# cpuboard.net
KiCad netlist of a schematic drawn in Altium Designer
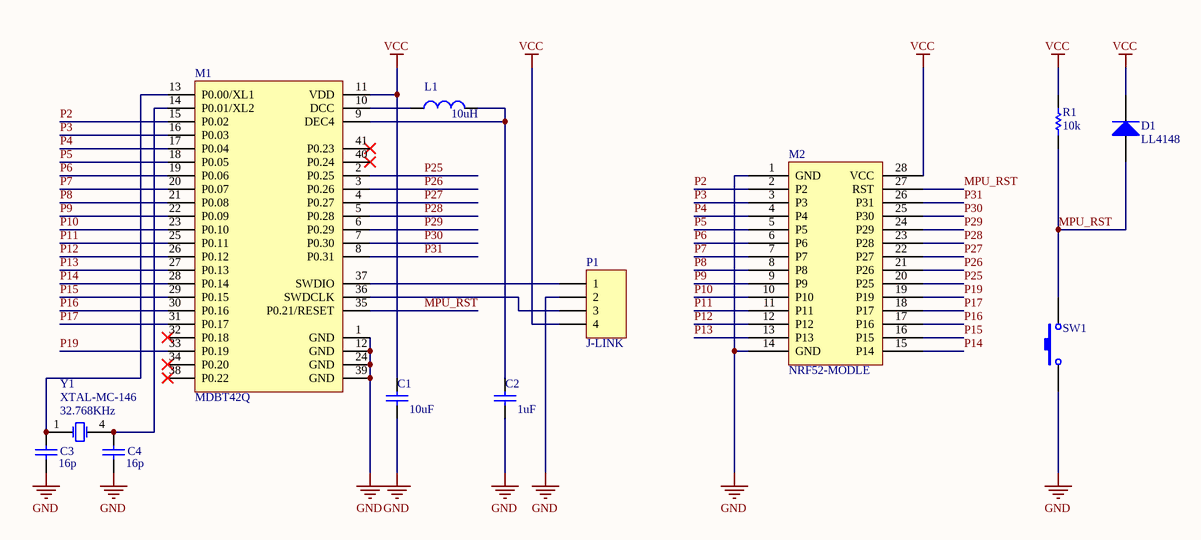
[diagram p0: cpuboard.SchDoc]

(export (version "E")
  (design (tool "Eeschema 10.0.6"))
  (components
    (comp (ref "C1")
      (value "10uF")
      (footprint "1608[0603]")
      (fields (field (name "Comment") "Cap1"))
      (libsource (lib "Other") (part "Cap1"))
    )
    (comp (ref "C2")
      (value "1uF")
      (footprint "1608[0603]")
      (fields (field (name "Comment") "Cap1"))
      (libsource (lib "Other") (part "Cap1"))
    )
    (comp (ref "C3")
      (value "16p")
      (footprint "1608[0603]")
      (fields (field (name "Comment") "Cap1"))
      (libsource (lib "Other") (part "Cap1"))
    )
    (comp (ref "C4")
      (value "16p")
      (footprint "1608[0603]")
      (fields (field (name "Comment") "Cap1"))
      (libsource (lib "Other") (part "Cap1"))
    )
    (comp (ref "D1") (value "LL4148") (footprint "SOD80") (libsource (lib "Diode") (part "LL4148")))
    (comp (ref "L1")
      (value "10uH")
      (footprint "2012[0805]")
      (fields (field (name "Comment") "Inductor"))
      (libsource (lib "Other") (part "Inductor"))
    )
    (comp (ref "M1") (value "MDBT42Q") (footprint "MDBT42Q") (libsource (lib "Module") (part "MDBT42Q")))
    (comp (ref "M2")
      (value "NRF52-MODLE")
      (footprint "NRF52-MODLE")
      (libsource (lib "newlib") (part "NRF52-MODLE"))
    )
    (comp (ref "P1")
      (value "J-LINK")
      (footprint "HDR1X4")
      (description "Header, 4-Pin")
      (fields (field (name "PUBLISHER") "Altium Limited"))
      (libsource (lib "Connector") (part "Header 4"))
    )
    (comp (ref "R1")
      (value "10k")
      (footprint "1608[0603]")
      (fields (field (name "Comment") "Res"))
      (libsource (lib "Other") (part "Res"))
    )
    (comp (ref "SW1")
      (value "TL3342F160QG")
      (footprint "TL3342F160QG")
      (libsource (lib "Switch") (part "TL3342F160QG"))
    )
    (comp (ref "Y1")
      (value "XTAL-MC-146")
      (footprint "MC-146")
      (fields (field (name "ALTIUM_VALUE") "32.768KHz"))
      (libsource (lib "Signal") (part "XTAL-MC-146"))
    )
  )
  (nets
    (net (code "1") (name "/MPU_RST") (class "Default")
      (node (ref "D1") (pin "1") (pinfunction "A_1") (pintype "passive"))
      (node (ref "M1") (pin "35") (pinfunction "P0.21/RESET_35") (pintype "passive"))
      (node (ref "M2") (pin "27") (pinfunction "RST_27") (pintype "passive"))
      (node (ref "R1") (pin "2") (pinfunction "2_2") (pintype "passive"))
      (node (ref "SW1") (pin "3") (pinfunction "3_3") (pintype "passive"))
    )
    (net (code "2") (name "/P2") (class "Default")
      (node (ref "M1") (pin "15") (pinfunction "P0.02_15") (pintype "passive"))
      (node (ref "M2") (pin "2") (pinfunction "P2_2") (pintype "passive"))
    )
    (net (code "3") (name "/P3") (class "Default")
      (node (ref "M1") (pin "16") (pinfunction "P0.03_16") (pintype "passive"))
      (node (ref "M2") (pin "3") (pinfunction "P3_3") (pintype "passive"))
    )
    (net (code "4") (name "/P4") (class "Default")
      (node (ref "M1") (pin "17") (pinfunction "P0.04_17") (pintype "passive"))
      (node (ref "M2") (pin "4") (pinfunction "P4_4") (pintype "passive"))
    )
    (net (code "5") (name "/P5") (class "Default")
      (node (ref "M1") (pin "18") (pinfunction "P0.05_18") (pintype "passive"))
      (node (ref "M2") (pin "5") (pinfunction "P5_5") (pintype "passive"))
    )
    (net (code "6") (name "/P6") (class "Default")
      (node (ref "M1") (pin "19") (pinfunction "P0.06_19") (pintype "passive"))
      (node (ref "M2") (pin "6") (pinfunction "P6_6") (pintype "passive"))
    )
    (net (code "7") (name "/P7") (class "Default")
      (node (ref "M1") (pin "20") (pinfunction "P0.07_20") (pintype "passive"))
      (node (ref "M2") (pin "7") (pinfunction "P7_7") (pintype "passive"))
    )
    (net (code "8") (name "/P8") (class "Default")
      (node (ref "M1") (pin "21") (pinfunction "P0.08_21") (pintype "passive"))
      (node (ref "M2") (pin "8") (pinfunction "P8_8") (pintype "passive"))
    )
    (net (code "9") (name "/P9") (class "Default")
      (node (ref "M1") (pin "22") (pinfunction "P0.09_22") (pintype "passive"))
      (node (ref "M2") (pin "9") (pinfunction "P9_9") (pintype "passive"))
    )
    (net (code "10") (name "/P10") (class "Default")
      (node (ref "M1") (pin "23") (pinfunction "P0.10_23") (pintype "passive"))
      (node (ref "M2") (pin "10") (pinfunction "P10_10") (pintype "passive"))
    )
    (net (code "11") (name "/P11") (class "Default")
      (node (ref "M1") (pin "25") (pinfunction "P0.11_25") (pintype "passive"))
      (node (ref "M2") (pin "11") (pinfunction "P11_11") (pintype "passive"))
    )
    (net (code "12") (name "/P12") (class "Default")
      (node (ref "M1") (pin "26") (pinfunction "P0.12_26") (pintype "passive"))
      (node (ref "M2") (pin "12") (pinfunction "P12_12") (pintype "passive"))
    )
    (net (code "13") (name "/P13") (class "Default")
      (node (ref "M1") (pin "27") (pinfunction "P0.13_27") (pintype "passive"))
      (node (ref "M2") (pin "13") (pinfunction "P13_13") (pintype "passive"))
    )
    (net (code "14") (name "/P14") (class "Default")
      (node (ref "M1") (pin "28") (pinfunction "P0.14_28") (pintype "passive"))
      (node (ref "M2") (pin "15") (pinfunction "P14_15") (pintype "passive"))
    )
    (net (code "15") (name "/P15") (class "Default")
      (node (ref "M1") (pin "29") (pinfunction "P0.15_29") (pintype "passive"))
      (node (ref "M2") (pin "16") (pinfunction "P15_16") (pintype "passive"))
    )
    (net (code "16") (name "/P16") (class "Default")
      (node (ref "M1") (pin "30") (pinfunction "P0.16_30") (pintype "passive"))
      (node (ref "M2") (pin "17") (pinfunction "P16_17") (pintype "passive"))
    )
    (net (code "17") (name "/P17") (class "Default")
      (node (ref "M1") (pin "31") (pinfunction "P0.17_31") (pintype "passive"))
      (node (ref "M2") (pin "18") (pinfunction "P17_18") (pintype "passive"))
    )
    (net (code "18") (name "/P19") (class "Default")
      (node (ref "M1") (pin "33") (pinfunction "P0.19_33") (pintype "passive"))
      (node (ref "M2") (pin "19") (pinfunction "P19_19") (pintype "passive"))
    )
    (net (code "19") (name "/P25") (class "Default")
      (node (ref "M1") (pin "2") (pinfunction "P0.25_2") (pintype "passive"))
      (node (ref "M2") (pin "20") (pinfunction "P25_20") (pintype "passive"))
    )
    (net (code "20") (name "/P26") (class "Default")
      (node (ref "M1") (pin "3") (pinfunction "P0.26_3") (pintype "passive"))
      (node (ref "M2") (pin "21") (pinfunction "P26_21") (pintype "passive"))
    )
    (net (code "21") (name "/P27") (class "Default")
      (node (ref "M1") (pin "4") (pinfunction "P0.27_4") (pintype "passive"))
      (node (ref "M2") (pin "22") (pinfunction "P27_22") (pintype "passive"))
    )
    (net (code "22") (name "/P28") (class "Default")
      (node (ref "M1") (pin "5") (pinfunction "P0.28_5") (pintype "passive"))
      (node (ref "M2") (pin "23") (pinfunction "P28_23") (pintype "passive"))
    )
    (net (code "23") (name "/P29") (class "Default")
      (node (ref "M1") (pin "6") (pinfunction "P0.29_6") (pintype "passive"))
      (node (ref "M2") (pin "24") (pinfunction "P29_24") (pintype "passive"))
    )
    (net (code "24") (name "/P30") (class "Default")
      (node (ref "M1") (pin "7") (pinfunction "P0.30_7") (pintype "passive"))
      (node (ref "M2") (pin "25") (pinfunction "P30_25") (pintype "passive"))
    )
    (net (code "25") (name "/P31") (class "Default")
      (node (ref "M1") (pin "8") (pinfunction "P0.31_8") (pintype "passive"))
      (node (ref "M2") (pin "26") (pinfunction "P31_26") (pintype "passive"))
    )
    (net (code "26") (name "GND") (class "Default")
      (node (ref "C1") (pin "1") (pinfunction "1_1") (pintype "passive"))
      (node (ref "C2") (pin "1") (pinfunction "1_1") (pintype "passive"))
      (node (ref "C3") (pin "1") (pinfunction "1_1") (pintype "passive"))
      (node (ref "C4") (pin "1") (pinfunction "1_1") (pintype "passive"))
      (node (ref "M1") (pin "1") (pinfunction "GND_1") (pintype "passive"))
      (node (ref "M1") (pin "12") (pinfunction "GND_12") (pintype "passive"))
      (node (ref "M1") (pin "24") (pinfunction "GND_24") (pintype "passive"))
      (node (ref "M1") (pin "39") (pinfunction "GND_39") (pintype "passive"))
      (node (ref "M2") (pin "1") (pinfunction "GND_1") (pintype "passive"))
      (node (ref "M2") (pin "14") (pinfunction "GND_14") (pintype "passive"))
      (node (ref "P1") (pin "2") (pinfunction "2_2") (pintype "passive"))
      (node (ref "SW1") (pin "1") (pinfunction "1_1") (pintype "passive"))
    )
    (net (code "27") (name "Net-(M1-DCC)") (class "Default")
      (node (ref "L1") (pin "1") (pinfunction "1_1") (pintype "passive"))
      (node (ref "M1") (pin "10") (pinfunction "DCC_10") (pintype "passive"))
    )
    (net (code "28") (name "Net-(M1-DEC4)") (class "Default")
      (node (ref "C2") (pin "2") (pinfunction "2_2") (pintype "passive"))
      (node (ref "L1") (pin "2") (pinfunction "2_2") (pintype "passive"))
      (node (ref "M1") (pin "9") (pinfunction "DEC4_9") (pintype "passive"))
    )
    (net (code "29") (name "Net-(M1-P0.00{slash}XL1)") (class "Default")
      (node (ref "C3") (pin "2") (pinfunction "2_2") (pintype "passive"))
      (node (ref "M1") (pin "13") (pinfunction "P0.00/XL1_13") (pintype "passive"))
      (node (ref "Y1") (pin "1") (pinfunction "OSC1_1") (pintype "passive"))
    )
    (net (code "30") (name "Net-(M1-P0.01{slash}XL2)") (class "Default")
      (node (ref "C4") (pin "2") (pinfunction "2_2") (pintype "passive"))
      (node (ref "M1") (pin "14") (pinfunction "P0.01/XL2_14") (pintype "passive"))
      (node (ref "Y1") (pin "4") (pinfunction "OSC2_4") (pintype "passive"))
    )
    (net (code "31") (name "Net-(M1-SWDCLK)") (class "Default")
      (node (ref "M1") (pin "36") (pinfunction "SWDCLK_36") (pintype "passive"))
      (node (ref "P1") (pin "3") (pinfunction "3_3") (pintype "passive"))
    )
    (net (code "32") (name "Net-(M1-SWDIO)") (class "Default")
      (node (ref "M1") (pin "37") (pinfunction "SWDIO_37") (pintype "passive"))
      (node (ref "P1") (pin "1") (pinfunction "1_1") (pintype "passive"))
    )
    (net (code "33") (name "VCC") (class "Default")
      (node (ref "C1") (pin "2") (pinfunction "2_2") (pintype "passive"))
      (node (ref "D1") (pin "2") (pinfunction "K_2") (pintype "passive"))
      (node (ref "M1") (pin "11") (pinfunction "VDD_11") (pintype "passive"))
      (node (ref "M2") (pin "28") (pinfunction "VCC_28") (pintype "passive"))
      (node (ref "P1") (pin "4") (pinfunction "4_4") (pintype "passive"))
      (node (ref "R1") (pin "1") (pinfunction "1_1") (pintype "passive"))
    )
    (net (code "34") (name "unconnected-(M1-P0.18-Pad32)") (class "Default")
      (node (ref "M1") (pin "32") (pinfunction "P0.18_32") (pintype "passive+no_connect"))
    )
    (net (code "35") (name "unconnected-(M1-P0.20-Pad34)") (class "Default")
      (node (ref "M1") (pin "34") (pinfunction "P0.20_34") (pintype "passive+no_connect"))
    )
    (net (code "36") (name "unconnected-(M1-P0.22-Pad38)") (class "Default")
      (node (ref "M1") (pin "38") (pinfunction "P0.22_38") (pintype "passive+no_connect"))
    )
    (net (code "37") (name "unconnected-(M1-P0.23-Pad41)") (class "Default")
      (node (ref "M1") (pin "41") (pinfunction "P0.23_41") (pintype "passive+no_connect"))
    )
    (net (code "38") (name "unconnected-(M1-P0.24-Pad40)") (class "Default")
      (node (ref "M1") (pin "40") (pinfunction "P0.24_40") (pintype "passive+no_connect"))
    )
  )
)
